# X_Y_Motor_Drivers.net
KiCad netlist of a schematic drawn in Altium Designer
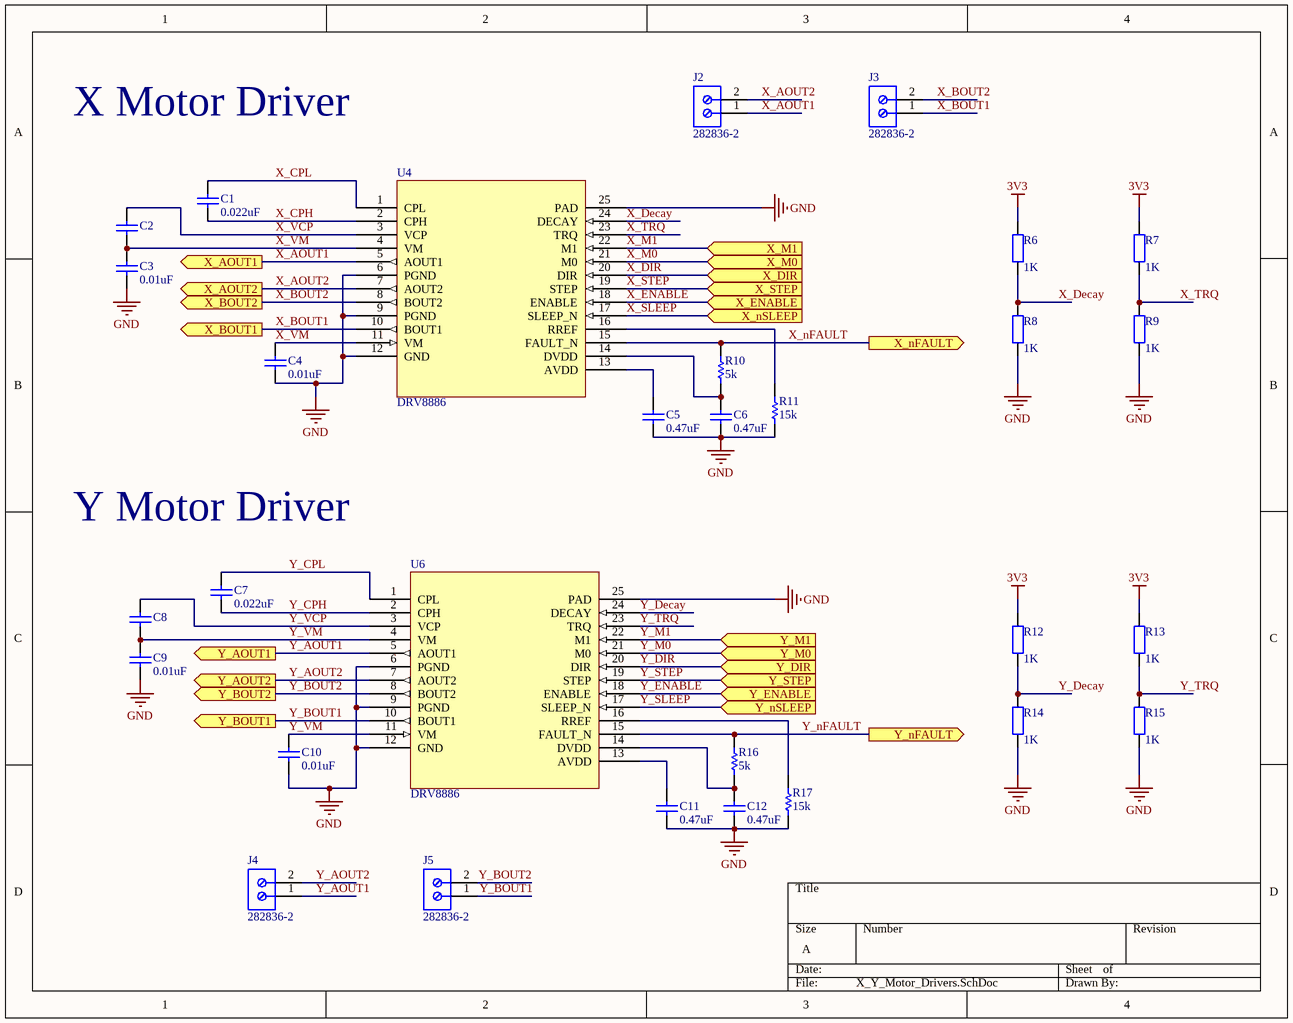
[diagram p0: X_Y_Motor_Drivers.SchDoc]

(export (version "E")
  (design (tool "Eeschema 10.0.6"))
  (components
    (comp (ref "C1")
      (value "0.022uF")
      (footprint "CAPC1608X87X35ML15T15")
      (fields (field (name "PART NUMBER") "C0603C223K4RACTU") (field (name "MANUFACTURER") "Kemet"))
      (libsource (lib "Altium Content Vault") (part "CAP"))
    )
    (comp (ref "C2")
      (value "0.22uF")
      (footprint "TDK-C1608-2_A_M")
      (description "Cap Ceramic, 0.22 uF, +/- 10%, -55 to 125 degC, 2-Pin SMD (0603), RoHS, Tape and Reel")
      (fields (field (name "MANUFACTURER") "TDK") (field (name "TOLERANCE") "±10%"))
      (libsource (lib "Altium Content Vault") (part "CAP-NP-2"))
    )
    (comp (ref "C3")
      (value "0.01uF")
      (footprint "CAPC1608X87X35LL15T15")
      (fields (field (name "MANUFACTURER") "Kemet") (field (name "PART NUMBER") "C0603X103K5RACTU"))
      (libsource (lib "Altium Content Vault") (part "CAP"))
    )
    (comp (ref "C4")
      (value "0.01uF")
      (footprint "CAPC1608X87X35LL15T15")
      (fields (field (name "MANUFACTURER") "Kemet") (field (name "PART NUMBER") "C0603X103K5RACTU"))
      (libsource (lib "Altium Content Vault") (part "CAP"))
    )
    (comp (ref "C5")
      (value "0.47uF")
      (footprint "CAPC1608X90X35ML15T15")
      (fields
        (field (name "PART NUMBER") "06033C474KAT2A")
        (field (name "MANUFACTURER") "AVX Interconnect / Elco")
      )
      (libsource (lib "Altium Content Vault") (part "CAP"))
    )
    (comp (ref "C6")
      (value "0.47uF")
      (footprint "CAPC1608X90X35ML15T15")
      (fields
        (field (name "PART NUMBER") "06033C474KAT2A")
        (field (name "MANUFACTURER") "AVX Interconnect / Elco")
      )
      (libsource (lib "Altium Content Vault") (part "CAP"))
    )
    (comp (ref "C7")
      (value "0.022uF")
      (footprint "CAPC1608X87X35ML15T15")
      (fields (field (name "PART NUMBER") "C0603C223K4RACTU") (field (name "MANUFACTURER") "Kemet"))
      (libsource (lib "Altium Content Vault") (part "CAP"))
    )
    (comp (ref "C8")
      (value "0.22uF")
      (footprint "TDK-C1608-2_A_M")
      (description "Cap Ceramic, 0.22 uF, +/- 10%, -55 to 125 degC, 2-Pin SMD (0603), RoHS, Tape and Reel")
      (fields (field (name "MANUFACTURER") "TDK") (field (name "TOLERANCE") "±10%"))
      (libsource (lib "Altium Content Vault") (part "CAP-NP-2"))
    )
    (comp (ref "C9")
      (value "0.01uF")
      (footprint "CAPC1608X87X35LL15T15")
      (fields (field (name "MANUFACTURER") "Kemet") (field (name "PART NUMBER") "C0603X103K5RACTU"))
      (libsource (lib "Altium Content Vault") (part "CAP"))
    )
    (comp (ref "C10")
      (value "0.01uF")
      (footprint "CAPC1608X87X35LL15T15")
      (fields (field (name "MANUFACTURER") "Kemet") (field (name "PART NUMBER") "C0603X103K5RACTU"))
      (libsource (lib "Altium Content Vault") (part "CAP"))
    )
    (comp (ref "C11")
      (value "0.47uF")
      (footprint "CAPC1608X90X35ML15T15")
      (fields
        (field (name "PART NUMBER") "06033C474KAT2A")
        (field (name "MANUFACTURER") "AVX Interconnect / Elco")
      )
      (libsource (lib "Altium Content Vault") (part "CAP"))
    )
    (comp (ref "C12")
      (value "0.47uF")
      (footprint "CAPC1608X90X35ML15T15")
      (fields
        (field (name "PART NUMBER") "06033C474KAT2A")
        (field (name "MANUFACTURER") "AVX Interconnect / Elco")
      )
      (libsource (lib "Altium Content Vault") (part "CAP"))
    )
    (comp (ref "J2")
      (value "282836-2")
      (footprint "TECO-282836-2_V")
      (description "Female Header, Pitch 5 mm, 1 x 2 Position, Height 10 mm, Tail Length 3.5 mm, Rohs, Bulk")
      (fields (field (name "VOLTAGE") "300V") (field (name "MANUFACTURER") "TE Connectivity"))
      (libsource (lib "Altium Content Vault") (part "CN-1P-F-TB2"))
    )
    (comp (ref "J3")
      (value "282836-2")
      (footprint "TECO-282836-2_V")
      (description "Female Header, Pitch 5 mm, 1 x 2 Position, Height 10 mm, Tail Length 3.5 mm, Rohs, Bulk")
      (fields (field (name "VOLTAGE") "300V") (field (name "MANUFACTURER") "TE Connectivity"))
      (libsource (lib "Altium Content Vault") (part "CN-1P-F-TB2"))
    )
    (comp (ref "J4")
      (value "282836-2")
      (footprint "TECO-282836-2_V")
      (description "Female Header, Pitch 5 mm, 1 x 2 Position, Height 10 mm, Tail Length 3.5 mm, Rohs, Bulk")
      (fields (field (name "VOLTAGE") "300V") (field (name "MANUFACTURER") "TE Connectivity"))
      (libsource (lib "Altium Content Vault") (part "CN-1P-F-TB2"))
    )
    (comp (ref "J5")
      (value "282836-2")
      (footprint "TECO-282836-2_V")
      (description "Female Header, Pitch 5 mm, 1 x 2 Position, Height 10 mm, Tail Length 3.5 mm, Rohs, Bulk")
      (fields (field (name "VOLTAGE") "300V") (field (name "MANUFACTURER") "TE Connectivity"))
      (libsource (lib "Altium Content Vault") (part "CN-1P-F-TB2"))
    )
    (comp (ref "R6")
      (value "1K")
      (footprint "AXIAL-0.4")
      (description "Resistor")
      (fields (field (name "Comment") "?") (field (name "PUBLISHER") "Altium Limited"))
      (libsource (lib "Miscellaneous Devices") (part "Res2"))
    )
    (comp (ref "R7")
      (value "1K")
      (footprint "AXIAL-0.4")
      (description "Resistor")
      (fields (field (name "Comment") "?") (field (name "PUBLISHER") "Altium Limited"))
      (libsource (lib "Miscellaneous Devices") (part "Res2"))
    )
    (comp (ref "R8")
      (value "1K")
      (footprint "AXIAL-0.4")
      (description "Resistor")
      (fields (field (name "Comment") "Res2") (field (name "PUBLISHER") "Altium Limited"))
      (libsource (lib "Miscellaneous Devices") (part "Res2"))
    )
    (comp (ref "R9")
      (value "1K")
      (footprint "AXIAL-0.4")
      (description "Resistor")
      (fields (field (name "Comment") "Res2") (field (name "PUBLISHER") "Altium Limited"))
      (libsource (lib "Miscellaneous Devices") (part "Res2"))
    )
    (comp (ref "R10")
      (value "5k")
      (footprint "RESC1608X55X25ML10T15")
      (description "Chip Resistor, 0 Ohm, +/- 5%, 0.1 W, -55 to 155 degC, 0603 (1608 Metric), RoHS, Tape and Reel")
      (fields (field (name "TOLERANCE") "5%") (field (name "MANUFACTURER") "Yageo"))
      (libsource (lib "Altium Content Vault") (part "RES-2"))
    )
    (comp (ref "R11")
      (value "15k")
      (footprint "RESC1608X55X25ML10T15")
      (description "Chip Resistor, 0 Ohm, +/- 5%, 0.1 W, -55 to 155 degC, 0603 (1608 Metric), RoHS, Tape and Reel")
      (fields (field (name "TOLERANCE") "5%") (field (name "MANUFACTURER") "Yageo"))
      (libsource (lib "Altium Content Vault") (part "RES-2"))
    )
    (comp (ref "R12")
      (value "1K")
      (footprint "AXIAL-0.4")
      (description "Resistor")
      (fields (field (name "Comment") "?") (field (name "PUBLISHER") "Altium Limited"))
      (libsource (lib "Miscellaneous Devices") (part "Res2"))
    )
    (comp (ref "R13")
      (value "1K")
      (footprint "AXIAL-0.4")
      (description "Resistor")
      (fields (field (name "Comment") "?") (field (name "PUBLISHER") "Altium Limited"))
      (libsource (lib "Miscellaneous Devices") (part "Res2"))
    )
    (comp (ref "R14")
      (value "1K")
      (footprint "AXIAL-0.4")
      (description "Resistor")
      (fields (field (name "Comment") "Res2") (field (name "PUBLISHER") "Altium Limited"))
      (libsource (lib "Miscellaneous Devices") (part "Res2"))
    )
    (comp (ref "R15")
      (value "1K")
      (footprint "AXIAL-0.4")
      (description "Resistor")
      (fields (field (name "Comment") "Res2") (field (name "PUBLISHER") "Altium Limited"))
      (libsource (lib "Miscellaneous Devices") (part "Res2"))
    )
    (comp (ref "R16")
      (value "5k")
      (footprint "RESC1608X55X25ML10T15")
      (description "Chip Resistor, 0 Ohm, +/- 5%, 0.1 W, -55 to 155 degC, 0603 (1608 Metric), RoHS, Tape and Reel")
      (fields (field (name "TOLERANCE") "5%") (field (name "MANUFACTURER") "Yageo"))
      (libsource (lib "Altium Content Vault") (part "RES-2"))
    )
    (comp (ref "R17")
      (value "15k")
      (footprint "RESC1608X55X25ML10T15")
      (description "Chip Resistor, 0 Ohm, +/- 5%, 0.1 W, -55 to 155 degC, 0603 (1608 Metric), RoHS, Tape and Reel")
      (fields (field (name "TOLERANCE") "5%") (field (name "MANUFACTURER") "Yageo"))
      (libsource (lib "Altium Content Vault") (part "RES-2"))
    )
    (comp (ref "U4")
      (value "DRV8886")
      (footprint "PWP0024B_N")
      (libsource (lib "TI_DRV8886") (part "DRV8886"))
    )
    (comp (ref "U6")
      (value "DRV8886")
      (footprint "PWP0024B_N")
      (libsource (lib "TI_DRV8886") (part "DRV8886"))
    )
  )
  (nets
    (net (code "1") (name "/X_AOUT1") (class "Default")
      (node (ref "J2") (pin "1") (pinfunction "1_1") (pintype "passive"))
      (node (ref "U4") (pin "5") (pinfunction "AOUT1_5") (pintype "output"))
    )
    (net (code "2") (name "/X_AOUT2") (class "Default")
      (node (ref "J2") (pin "2") (pinfunction "2_2") (pintype "passive"))
      (node (ref "U4") (pin "7") (pinfunction "AOUT2_7") (pintype "output"))
    )
    (net (code "3") (name "/X_BOUT1") (class "Default")
      (node (ref "J3") (pin "1") (pinfunction "1_1") (pintype "passive"))
      (node (ref "U4") (pin "10") (pinfunction "BOUT1_10") (pintype "output"))
    )
    (net (code "4") (name "/X_BOUT2") (class "Default")
      (node (ref "J3") (pin "2") (pinfunction "2_2") (pintype "passive"))
      (node (ref "U4") (pin "8") (pinfunction "BOUT2_8") (pintype "output"))
    )
    (net (code "5") (name "/X_CPH") (class "Default")
      (node (ref "C1") (pin "1") (pinfunction "1_1") (pintype "passive"))
      (node (ref "U4") (pin "2") (pinfunction "CPH_2") (pintype "passive"))
    )
    (net (code "6") (name "/X_CPL") (class "Default")
      (node (ref "C1") (pin "2") (pinfunction "2_2") (pintype "passive"))
      (node (ref "U4") (pin "1") (pinfunction "CPL_1") (pintype "passive"))
    )
    (net (code "7") (name "/X_DIR") (class "Default")
      (node (ref "U4") (pin "20") (pinfunction "DIR_20") (pintype "input"))
    )
    (net (code "8") (name "/X_Decay") (class "Default")
      (node (ref "R6") (pin "1") (pinfunction "1_1") (pintype "passive"))
      (node (ref "R8") (pin "2") (pinfunction "2_2") (pintype "passive"))
      (node (ref "U4") (pin "24") (pinfunction "DECAY_24") (pintype "input"))
    )
    (net (code "9") (name "/X_ENABLE") (class "Default")
      (node (ref "U4") (pin "18") (pinfunction "ENABLE_18") (pintype "input"))
    )
    (net (code "10") (name "/X_M0") (class "Default")
      (node (ref "U4") (pin "21") (pinfunction "M0_21") (pintype "input"))
    )
    (net (code "11") (name "/X_M1") (class "Default")
      (node (ref "U4") (pin "22") (pinfunction "M1_22") (pintype "input"))
    )
    (net (code "12") (name "/X_STEP") (class "Default")
      (node (ref "U4") (pin "19") (pinfunction "STEP_19") (pintype "input"))
    )
    (net (code "13") (name "/X_TRQ") (class "Default")
      (node (ref "R7") (pin "1") (pinfunction "1_1") (pintype "passive"))
      (node (ref "R9") (pin "2") (pinfunction "2_2") (pintype "passive"))
      (node (ref "U4") (pin "23") (pinfunction "TRQ_23") (pintype "input"))
    )
    (net (code "14") (name "/X_VCP") (class "Default")
      (node (ref "C2") (pin "2") (pinfunction "2_2") (pintype "passive"))
      (node (ref "U4") (pin "3") (pinfunction "VCP_3") (pintype "passive"))
    )
    (net (code "15") (name "/X_VM") (class "Default")
      (node (ref "C2") (pin "1") (pinfunction "1_1") (pintype "passive"))
      (node (ref "C3") (pin "1") (pinfunction "1_1") (pintype "passive"))
      (node (ref "C4") (pin "1") (pinfunction "1_1") (pintype "passive"))
      (node (ref "U4") (pin "11") (pinfunction "VM_11") (pintype "input"))
      (node (ref "U4") (pin "4") (pinfunction "VM_4") (pintype "passive"))
    )
    (net (code "16") (name "/X_nFAULT") (class "Default")
      (node (ref "R10") (pin "2") (pinfunction "2_2") (pintype "passive"))
      (node (ref "U4") (pin "15") (pinfunction "FAULT_N_15") (pintype "passive"))
    )
    (net (code "17") (name "/X~{_}SLEEP") (class "Default")
      (node (ref "U4") (pin "17") (pinfunction "SLEEP_N_17") (pintype "input"))
    )
    (net (code "18") (name "/Y_AOUT1") (class "Default")
      (node (ref "J4") (pin "1") (pinfunction "1_1") (pintype "passive"))
      (node (ref "U6") (pin "5") (pinfunction "AOUT1_5") (pintype "output"))
    )
    (net (code "19") (name "/Y_AOUT2") (class "Default")
      (node (ref "J4") (pin "2") (pinfunction "2_2") (pintype "passive"))
      (node (ref "U6") (pin "7") (pinfunction "AOUT2_7") (pintype "output"))
    )
    (net (code "20") (name "/Y_BOUT1") (class "Default")
      (node (ref "J5") (pin "1") (pinfunction "1_1") (pintype "passive"))
      (node (ref "U6") (pin "10") (pinfunction "BOUT1_10") (pintype "output"))
    )
    (net (code "21") (name "/Y_BOUT2") (class "Default")
      (node (ref "J5") (pin "2") (pinfunction "2_2") (pintype "passive"))
      (node (ref "U6") (pin "8") (pinfunction "BOUT2_8") (pintype "output"))
    )
    (net (code "22") (name "/Y_CPH") (class "Default")
      (node (ref "C7") (pin "1") (pinfunction "1_1") (pintype "passive"))
      (node (ref "U6") (pin "2") (pinfunction "CPH_2") (pintype "passive"))
    )
    (net (code "23") (name "/Y_CPL") (class "Default")
      (node (ref "C7") (pin "2") (pinfunction "2_2") (pintype "passive"))
      (node (ref "U6") (pin "1") (pinfunction "CPL_1") (pintype "passive"))
    )
    (net (code "24") (name "/Y_DIR") (class "Default")
      (node (ref "U6") (pin "20") (pinfunction "DIR_20") (pintype "input"))
    )
    (net (code "25") (name "/Y_Decay") (class "Default")
      (node (ref "R12") (pin "1") (pinfunction "1_1") (pintype "passive"))
      (node (ref "R14") (pin "2") (pinfunction "2_2") (pintype "passive"))
      (node (ref "U6") (pin "24") (pinfunction "DECAY_24") (pintype "input"))
    )
    (net (code "26") (name "/Y_ENABLE") (class "Default")
      (node (ref "U6") (pin "18") (pinfunction "ENABLE_18") (pintype "input"))
    )
    (net (code "27") (name "/Y_M0") (class "Default")
      (node (ref "U6") (pin "21") (pinfunction "M0_21") (pintype "input"))
    )
    (net (code "28") (name "/Y_M1") (class "Default")
      (node (ref "U6") (pin "22") (pinfunction "M1_22") (pintype "input"))
    )
    (net (code "29") (name "/Y_STEP") (class "Default")
      (node (ref "U6") (pin "19") (pinfunction "STEP_19") (pintype "input"))
    )
    (net (code "30") (name "/Y_TRQ") (class "Default")
      (node (ref "R13") (pin "1") (pinfunction "1_1") (pintype "passive"))
      (node (ref "R15") (pin "2") (pinfunction "2_2") (pintype "passive"))
      (node (ref "U6") (pin "23") (pinfunction "TRQ_23") (pintype "input"))
    )
    (net (code "31") (name "/Y_VCP") (class "Default")
      (node (ref "C8") (pin "2") (pinfunction "2_2") (pintype "passive"))
      (node (ref "U6") (pin "3") (pinfunction "VCP_3") (pintype "passive"))
    )
    (net (code "32") (name "/Y_VM") (class "Default")
      (node (ref "C10") (pin "1") (pinfunction "1_1") (pintype "passive"))
      (node (ref "C8") (pin "1") (pinfunction "1_1") (pintype "passive"))
      (node (ref "C9") (pin "1") (pinfunction "1_1") (pintype "passive"))
      (node (ref "U6") (pin "11") (pinfunction "VM_11") (pintype "input"))
      (node (ref "U6") (pin "4") (pinfunction "VM_4") (pintype "passive"))
    )
    (net (code "33") (name "/Y_nFAULT") (class "Default")
      (node (ref "R16") (pin "2") (pinfunction "2_2") (pintype "passive"))
      (node (ref "U6") (pin "15") (pinfunction "FAULT_N_15") (pintype "passive"))
    )
    (net (code "34") (name "/Y~{_}SLEEP") (class "Default")
      (node (ref "U6") (pin "17") (pinfunction "SLEEP_N_17") (pintype "input"))
    )
    (net (code "35") (name "3V3") (class "Default")
      (node (ref "R12") (pin "2") (pinfunction "2_2") (pintype "passive"))
      (node (ref "R13") (pin "2") (pinfunction "2_2") (pintype "passive"))
      (node (ref "R6") (pin "2") (pinfunction "2_2") (pintype "passive"))
      (node (ref "R7") (pin "2") (pinfunction "2_2") (pintype "passive"))
    )
    (net (code "36") (name "GND") (class "Default")
      (node (ref "C10") (pin "2") (pinfunction "2_2") (pintype "passive"))
      (node (ref "C11") (pin "1") (pinfunction "1_1") (pintype "passive"))
      (node (ref "C12") (pin "1") (pinfunction "1_1") (pintype "passive"))
      (node (ref "C3") (pin "2") (pinfunction "2_2") (pintype "passive"))
      (node (ref "C4") (pin "2") (pinfunction "2_2") (pintype "passive"))
      (node (ref "C5") (pin "1") (pinfunction "1_1") (pintype "passive"))
      (node (ref "C6") (pin "1") (pinfunction "1_1") (pintype "passive"))
      (node (ref "C9") (pin "2") (pinfunction "2_2") (pintype "passive"))
      (node (ref "R11") (pin "1") (pinfunction "1_1") (pintype "passive"))
      (node (ref "R14") (pin "1") (pinfunction "1_1") (pintype "passive"))
      (node (ref "R15") (pin "1") (pinfunction "1_1") (pintype "passive"))
      (node (ref "R17") (pin "1") (pinfunction "1_1") (pintype "passive"))
      (node (ref "R8") (pin "1") (pinfunction "1_1") (pintype "passive"))
      (node (ref "R9") (pin "1") (pinfunction "1_1") (pintype "passive"))
      (node (ref "U4") (pin "12") (pinfunction "GND_12") (pintype "passive"))
      (node (ref "U4") (pin "25") (pinfunction "PAD_25") (pintype "passive"))
      (node (ref "U4") (pin "6") (pinfunction "PGND_6") (pintype "passive"))
      (node (ref "U4") (pin "9") (pinfunction "PGND_9") (pintype "passive"))
      (node (ref "U6") (pin "12") (pinfunction "GND_12") (pintype "passive"))
      (node (ref "U6") (pin "25") (pinfunction "PAD_25") (pintype "passive"))
      (node (ref "U6") (pin "6") (pinfunction "PGND_6") (pintype "passive"))
      (node (ref "U6") (pin "9") (pinfunction "PGND_9") (pintype "passive"))
    )
    (net (code "37") (name "Net-(U4-AVDD)") (class "Default")
      (node (ref "C5") (pin "2") (pinfunction "2_2") (pintype "passive"))
      (node (ref "U4") (pin "13") (pinfunction "AVDD_13") (pintype "passive"))
    )
    (net (code "38") (name "Net-(U4-DVDD)") (class "Default")
      (node (ref "C6") (pin "2") (pinfunction "2_2") (pintype "passive"))
      (node (ref "R10") (pin "1") (pinfunction "1_1") (pintype "passive"))
      (node (ref "U4") (pin "14") (pinfunction "DVDD_14") (pintype "passive"))
    )
    (net (code "39") (name "Net-(U4-RREF)") (class "Default")
      (node (ref "R11") (pin "2") (pinfunction "2_2") (pintype "passive"))
      (node (ref "U4") (pin "16") (pinfunction "RREF_16") (pintype "passive"))
    )
    (net (code "40") (name "Net-(U6-AVDD)") (class "Default")
      (node (ref "C11") (pin "2") (pinfunction "2_2") (pintype "passive"))
      (node (ref "U6") (pin "13") (pinfunction "AVDD_13") (pintype "passive"))
    )
    (net (code "41") (name "Net-(U6-DVDD)") (class "Default")
      (node (ref "C12") (pin "2") (pinfunction "2_2") (pintype "passive"))
      (node (ref "R16") (pin "1") (pinfunction "1_1") (pintype "passive"))
      (node (ref "U6") (pin "14") (pinfunction "DVDD_14") (pintype "passive"))
    )
    (net (code "42") (name "Net-(U6-RREF)") (class "Default")
      (node (ref "R17") (pin "2") (pinfunction "2_2") (pintype "passive"))
      (node (ref "U6") (pin "16") (pinfunction "RREF_16") (pintype "passive"))
    )
  )
)
